# Sheet1.net
KiCad netlist of a schematic drawn in Altium Designer
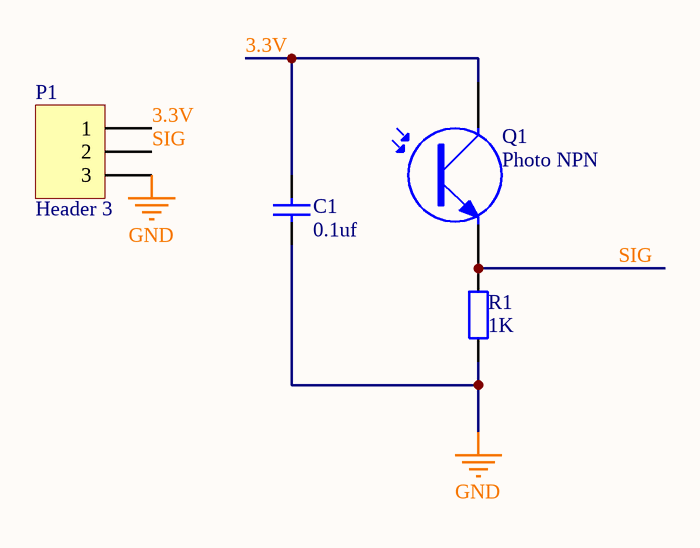
[diagram p0: Sheet1.SchDoc]

(export (version "E")
  (design (tool "Eeschema 10.0.6"))
  (components
    (comp (ref "C1")
      (value "0.1uf")
      (footprint "0603")
      (description "Capacitor")
      (fields (field (name "Comment") "Cap") (field (name "PUBLISHER") "Altium Limited"))
      (libsource (lib "Miscellaneous Devices") (part "Cap"))
    )
    (comp (ref "P1")
      (value "Header 3")
      (footprint "HDR1X3")
      (description "Header, 3-Pin")
      (fields (field (name "PUBLISHER") "Altium Limited"))
      (libsource (lib "Miscellaneous Connectors") (part "Header 3"))
    )
    (comp (ref "Q1")
      (value "Photo NPN")
      (footprint "1206-TEMT6000")
      (description "NPN Phototransistor")
      (fields (field (name "PUBLISHER") "Altium Limited"))
      (libsource (lib "Miscellaneous Devices") (part "Photo NPN"))
    )
    (comp (ref "R1")
      (value "1K")
      (footprint "0603")
      (description "Resistor")
      (fields (field (name "Comment") "Res2") (field (name "PUBLISHER") "Altium Limited"))
      (libsource (lib "Miscellaneous Devices") (part "Res2"))
    )
  )
  (nets
    (net (code "1") (name "/3.3V") (class "Default")
      (node (ref "C1") (pin "2") (pinfunction "2_2") (pintype "passive"))
      (node (ref "P1") (pin "1") (pinfunction "1_1") (pintype "passive"))
      (node (ref "Q1") (pin "1") (pinfunction "C_1") (pintype "passive"))
    )
    (net (code "2") (name "/SIG") (class "Default")
      (node (ref "P1") (pin "2") (pinfunction "2_2") (pintype "passive"))
      (node (ref "Q1") (pin "3") (pinfunction "E_3") (pintype "passive"))
      (node (ref "R1") (pin "2") (pinfunction "2_2") (pintype "passive"))
    )
    (net (code "3") (name "GND") (class "Default")
      (node (ref "C1") (pin "1") (pinfunction "1_1") (pintype "passive"))
      (node (ref "P1") (pin "3") (pinfunction "3_3") (pintype "passive"))
      (node (ref "R1") (pin "1") (pinfunction "1_1") (pintype "passive"))
    )
  )
)
